# Power.net
KiCad netlist of a schematic drawn in Altium Designer
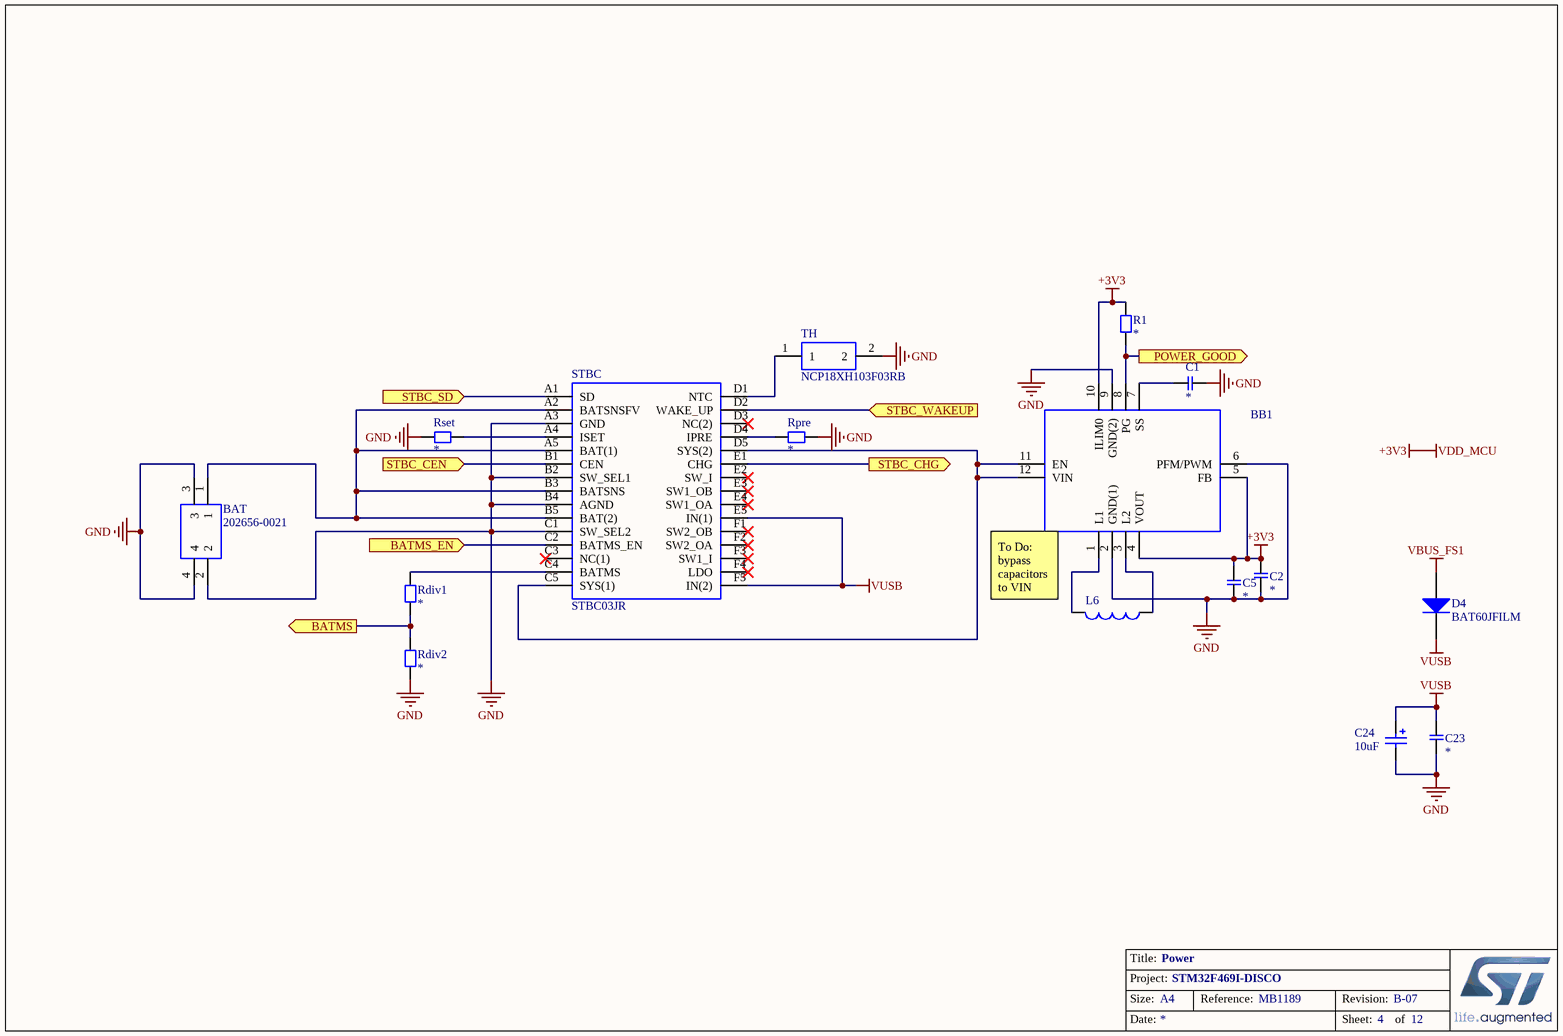
[diagram p0: Power.SchDoc]

(export (version "E")
  (design (tool "Eeschema 10.0.6"))
  (components
    (comp (ref "BAT")
      (value "202656-0021")
      (footprint "2026560021")
      (description "MOLEX - 202656-0021 - PLUG HOUSING, 2POS, NYLON, BLACK")
      (fields (field (name "MOUSER PART NUMBER") "538-202656-0021"))
      (libsource (lib "202656-0021") (part "202656-0021"))
    )
    (comp (ref "BB1")
      (value "TPS63051RMWT")
      (footprint "QFN50P250X250X100-12N-D")
      (description "Switching Voltage Regulators Tiny Single Ind Buck Boost Convter")
      (libsource (lib "TPS63051RMWT") (part "TPS63051RMWT"))
    )
    (comp (ref "C1")
      (value "1nF")
      (footprint "CAP - 0402")
      (fields (field (name "ALTIUM_VALUE") "*"))
      (libsource (lib "passives") (part "capacitor"))
    )
    (comp (ref "C2")
      (value "10uF")
      (footprint "CAP - 0402")
      (fields (field (name "ALTIUM_VALUE") "*"))
      (libsource (lib "passives") (part "capacitor"))
    )
    (comp (ref "C5")
      (value "100nF")
      (footprint "CAP - 0402")
      (fields (field (name "ALTIUM_VALUE") "*"))
      (libsource (lib "passives") (part "capacitor"))
    )
    (comp (ref "C23")
      (value "10uF")
      (footprint "CAP - 0402")
      (fields (field (name "ALTIUM_VALUE") "*"))
      (libsource (lib "passives") (part "capacitor"))
    )
    (comp (ref "C24")
      (value "10uF")
      (footprint "KEMET Electronics Footprints:A")
      (description "Polarized Capacitor (Radial)")
      (fields (field (name "PUBLISHER") "Altium Limited"))
      (libsource (lib "Miscellaneous Devices") (part "Cap Pol1"))
    )
    (comp (ref "D4")
      (value "BAT60JFILM")
      (footprint "SOD323")
      (libsource (lib "MCD_TOOLS") (part "BAT60JFILM"))
    )
    (comp (ref "L6")
      (value "1269AS-H-1R5M=P2")
      (footprint "INDC2928X203N")
      (description "Inductor")
      (fields (field (name "PUBLISHER") "Altium Limited"))
      (libsource (lib "Miscellaneous Devices") (part "Inductor"))
    )
    (comp (ref "R1")
      (value "1M")
      (footprint "RES - 1206")
      (fields (field (name "ALTIUM_VALUE") "*"))
      (libsource (lib "passives") (part "resistor"))
    )
    (comp (ref "Rdiv1")
      (value "100k")
      (footprint "RES - 0402")
      (fields (field (name "ALTIUM_VALUE") "*"))
      (libsource (lib "passives") (part "resistor"))
    )
    (comp (ref "Rdiv2")
      (value "200K")
      (footprint "RES - 0402")
      (fields (field (name "ALTIUM_VALUE") "*"))
      (libsource (lib "passives") (part "resistor"))
    )
    (comp (ref "Rpre")
      (value "1K")
      (footprint "RES - 0402")
      (fields (field (name "ALTIUM_VALUE") "*"))
      (libsource (lib "passives") (part "resistor"))
    )
    (comp (ref "Rset")
      (value "430 Ohm")
      (footprint "RES - 0402")
      (fields (field (name "ALTIUM_VALUE") "*"))
      (libsource (lib "passives") (part "resistor"))
    )
    (comp (ref "STBC")
      (value "STBC03JR")
      (footprint "BGA30C40P5X6_225X259X60")
      (description "STMICROELECTRONICS - STBC03JR - BATTERY CHARGER, LI-ION/POL, FLIPCHIP-30")
      (libsource (lib "STBC03JR") (part "STBC03JR"))
    )
    (comp (ref "TH")
      (value "NCP18XH103F03RB")
      (footprint "THRMC1608X95N")
      (description "Thermistor NTC 10K Ohm 1% 2-Pin 0603 Surface Mount Solder Pad 3434K T/R")
      (fields
        (field (name "RS PART NUMBER") "7259057P")
        (field (name "MOUSER PART NUMBER") "81-NCP18XH103F03RB")
      )
      (libsource (lib "NCP18XH103F03RB") (part "NCP18XH103F03RB"))
    )
  )
  (nets
    (net (code "1") (name "+3V3") (class "Default")
      (node (ref "BB1") (pin "10") (pinfunction "ILIM0_10") (pintype "passive"))
      (node (ref "BB1") (pin "4") (pinfunction "VOUT_4") (pintype "passive"))
      (node (ref "BB1") (pin "5") (pinfunction "FB_5") (pintype "passive"))
      (node (ref "C2") (pin "1") (pinfunction "1_1") (pintype "passive"))
      (node (ref "C5") (pin "1") (pinfunction "1_1") (pintype "passive"))
      (node (ref "R1") (pin "1") (pinfunction "1_1") (pintype "passive"))
    )
    (net (code "2") (name "/BATMS") (class "Default")
      (node (ref "Rdiv1") (pin "1") (pinfunction "1_1") (pintype "passive"))
      (node (ref "Rdiv2") (pin "2") (pinfunction "2_2") (pintype "passive"))
    )
    (net (code "3") (name "/BATMS_EN") (class "Default")
      (node (ref "STBC") (pin "C2") (pinfunction "BATMS_EN_C2") (pintype "passive"))
    )
    (net (code "4") (name "/POWER_GOOD") (class "Default")
      (node (ref "BB1") (pin "8") (pinfunction "PG_8") (pintype "passive"))
      (node (ref "R1") (pin "2") (pinfunction "2_2") (pintype "passive"))
    )
    (net (code "5") (name "/STBC_CEN") (class "Default")
      (node (ref "STBC") (pin "B1") (pinfunction "CEN_B1") (pintype "passive"))
    )
    (net (code "6") (name "/STBC_CHG") (class "Default")
      (node (ref "STBC") (pin "E1") (pinfunction "CHG_E1") (pintype "passive"))
    )
    (net (code "7") (name "/STBC_SD") (class "Default")
      (node (ref "STBC") (pin "A1") (pinfunction "SD_A1") (pintype "passive"))
    )
    (net (code "8") (name "/STBC_WAKEUP") (class "Default")
      (node (ref "STBC") (pin "D2") (pinfunction "WAKE_UP_D2") (pintype "passive"))
    )
    (net (code "9") (name "GND") (class "Default")
      (node (ref "BAT") (pin "2") (pinfunction "2_2") (pintype "passive"))
      (node (ref "BAT") (pin "3") (pinfunction "3_3") (pintype "passive"))
      (node (ref "BAT") (pin "4") (pinfunction "4_4") (pintype "passive"))
      (node (ref "BB1") (pin "2") (pinfunction "GND(1)_2") (pintype "passive"))
      (node (ref "BB1") (pin "6") (pinfunction "PFM/PWM_6") (pintype "passive"))
      (node (ref "BB1") (pin "9") (pinfunction "GND(2)_9") (pintype "passive"))
      (node (ref "C1") (pin "2") (pinfunction "2_2") (pintype "passive"))
      (node (ref "C2") (pin "2") (pinfunction "2_2") (pintype "passive"))
      (node (ref "C23") (pin "2") (pinfunction "2_2") (pintype "passive"))
      (node (ref "C24") (pin "2") (pinfunction "2_2") (pintype "passive"))
      (node (ref "C5") (pin "2") (pinfunction "2_2") (pintype "passive"))
      (node (ref "Rdiv2") (pin "1") (pinfunction "1_1") (pintype "passive"))
      (node (ref "Rpre") (pin "1") (pinfunction "1_1") (pintype "passive"))
      (node (ref "Rset") (pin "2") (pinfunction "2_2") (pintype "passive"))
      (node (ref "STBC") (pin "A3") (pinfunction "GND_A3") (pintype "passive"))
      (node (ref "STBC") (pin "B2") (pinfunction "SW_SEL1_B2") (pintype "passive"))
      (node (ref "STBC") (pin "B4") (pinfunction "AGND_B4") (pintype "passive"))
      (node (ref "STBC") (pin "C1") (pinfunction "SW_SEL2_C1") (pintype "passive"))
      (node (ref "TH") (pin "2") (pinfunction "2_2") (pintype "passive"))
    )
    (net (code "10") (name "Net-(BB1-EN)") (class "Default")
      (node (ref "BB1") (pin "11") (pinfunction "EN_11") (pintype "passive"))
      (node (ref "BB1") (pin "12") (pinfunction "VIN_12") (pintype "passive"))
      (node (ref "STBC") (pin "C5") (pinfunction "SYS(1)_C5") (pintype "passive"))
      (node (ref "STBC") (pin "D5") (pinfunction "SYS(2)_D5") (pintype "passive"))
    )
    (net (code "11") (name "Net-(BB1-L1)") (class "Default")
      (node (ref "BB1") (pin "1") (pinfunction "L1_1") (pintype "passive"))
      (node (ref "L6") (pin "2") (pinfunction "2_2") (pintype "passive"))
    )
    (net (code "12") (name "Net-(BB1-L2)") (class "Default")
      (node (ref "BB1") (pin "3") (pinfunction "L2_3") (pintype "passive"))
      (node (ref "L6") (pin "1") (pinfunction "1_1") (pintype "passive"))
    )
    (net (code "13") (name "Net-(BB1-SS)") (class "Default")
      (node (ref "BB1") (pin "7") (pinfunction "SS_7") (pintype "passive"))
      (node (ref "C1") (pin "1") (pinfunction "1_1") (pintype "passive"))
    )
    (net (code "14") (name "Net-(STBC-BAT(1))") (class "Default")
      (node (ref "BAT") (pin "1") (pinfunction "1_1") (pintype "passive"))
      (node (ref "STBC") (pin "A2") (pinfunction "BATSNSFV_A2") (pintype "passive"))
      (node (ref "STBC") (pin "A5") (pinfunction "BAT(1)_A5") (pintype "passive"))
      (node (ref "STBC") (pin "B3") (pinfunction "BATSNS_B3") (pintype "passive"))
      (node (ref "STBC") (pin "B5") (pinfunction "BAT(2)_B5") (pintype "passive"))
    )
    (net (code "15") (name "Net-(STBC-BATMS)") (class "Default")
      (node (ref "Rdiv1") (pin "2") (pinfunction "2_2") (pintype "passive"))
      (node (ref "STBC") (pin "C4") (pinfunction "BATMS_C4") (pintype "passive"))
    )
    (net (code "16") (name "Net-(STBC-IPRE)") (class "Default")
      (node (ref "Rpre") (pin "2") (pinfunction "2_2") (pintype "passive"))
      (node (ref "STBC") (pin "D4") (pinfunction "IPRE_D4") (pintype "passive"))
    )
    (net (code "17") (name "Net-(STBC-ISET)") (class "Default")
      (node (ref "Rset") (pin "1") (pinfunction "1_1") (pintype "passive"))
      (node (ref "STBC") (pin "A4") (pinfunction "ISET_A4") (pintype "passive"))
    )
    (net (code "18") (name "Net-(STBC-NTC)") (class "Default")
      (node (ref "STBC") (pin "D1") (pinfunction "NTC_D1") (pintype "passive"))
      (node (ref "TH") (pin "1") (pinfunction "1_1") (pintype "passive"))
    )
    (net (code "19") (name "VBUS_FS1") (class "Default")
      (node (ref "D4") (pin "1") (pinfunction "A_1") (pintype "passive"))
    )
    (net (code "20") (name "VUSB") (class "Default")
      (node (ref "C23") (pin "1") (pinfunction "1_1") (pintype "passive"))
      (node (ref "C24") (pin "1") (pinfunction "1_1") (pintype "passive"))
      (node (ref "D4") (pin "2") (pinfunction "K_2") (pintype "passive"))
      (node (ref "STBC") (pin "E5") (pinfunction "IN(1)_E5") (pintype "passive"))
      (node (ref "STBC") (pin "F5") (pinfunction "IN(2)_F5") (pintype "passive"))
    )
    (net (code "21") (name "unconnected-(STBC-LDO-PadF4)") (class "Default")
      (node (ref "STBC") (pin "F4") (pinfunction "LDO_F4") (pintype "passive+no_connect"))
    )
    (net (code "22") (name "unconnected-(STBC-NC(1)-PadC3)") (class "Default")
      (node (ref "STBC") (pin "C3") (pinfunction "NC(1)_C3") (pintype "passive+no_connect"))
    )
    (net (code "23") (name "unconnected-(STBC-NC(2)-PadD3)") (class "Default")
      (node (ref "STBC") (pin "D3") (pinfunction "NC(2)_D3") (pintype "passive+no_connect"))
    )
    (net (code "24") (name "unconnected-(STBC-SW1_I-PadF3)") (class "Default")
      (node (ref "STBC") (pin "F3") (pinfunction "SW1_I_F3") (pintype "passive+no_connect"))
    )
    (net (code "25") (name "unconnected-(STBC-SW1_OA-PadE4)") (class "Default")
      (node (ref "STBC") (pin "E4") (pinfunction "SW1_OA_E4") (pintype "passive+no_connect"))
    )
    (net (code "26") (name "unconnected-(STBC-SW1_OB-PadE3)") (class "Default")
      (node (ref "STBC") (pin "E3") (pinfunction "SW1_OB_E3") (pintype "passive+no_connect"))
    )
    (net (code "27") (name "unconnected-(STBC-SW2_OA-PadF2)") (class "Default")
      (node (ref "STBC") (pin "F2") (pinfunction "SW2_OA_F2") (pintype "passive+no_connect"))
    )
    (net (code "28") (name "unconnected-(STBC-SW2_OB-PadF1)") (class "Default")
      (node (ref "STBC") (pin "F1") (pinfunction "SW2_OB_F1") (pintype "passive+no_connect"))
    )
    (net (code "29") (name "unconnected-(STBC-SW_I-PadE2)") (class "Default")
      (node (ref "STBC") (pin "E2") (pinfunction "SW_I_E2") (pintype "passive+no_connect"))
    )
  )
)
